# OPAMP_TESTER_1.net
KiCad netlist of a schematic drawn in Altium Designer
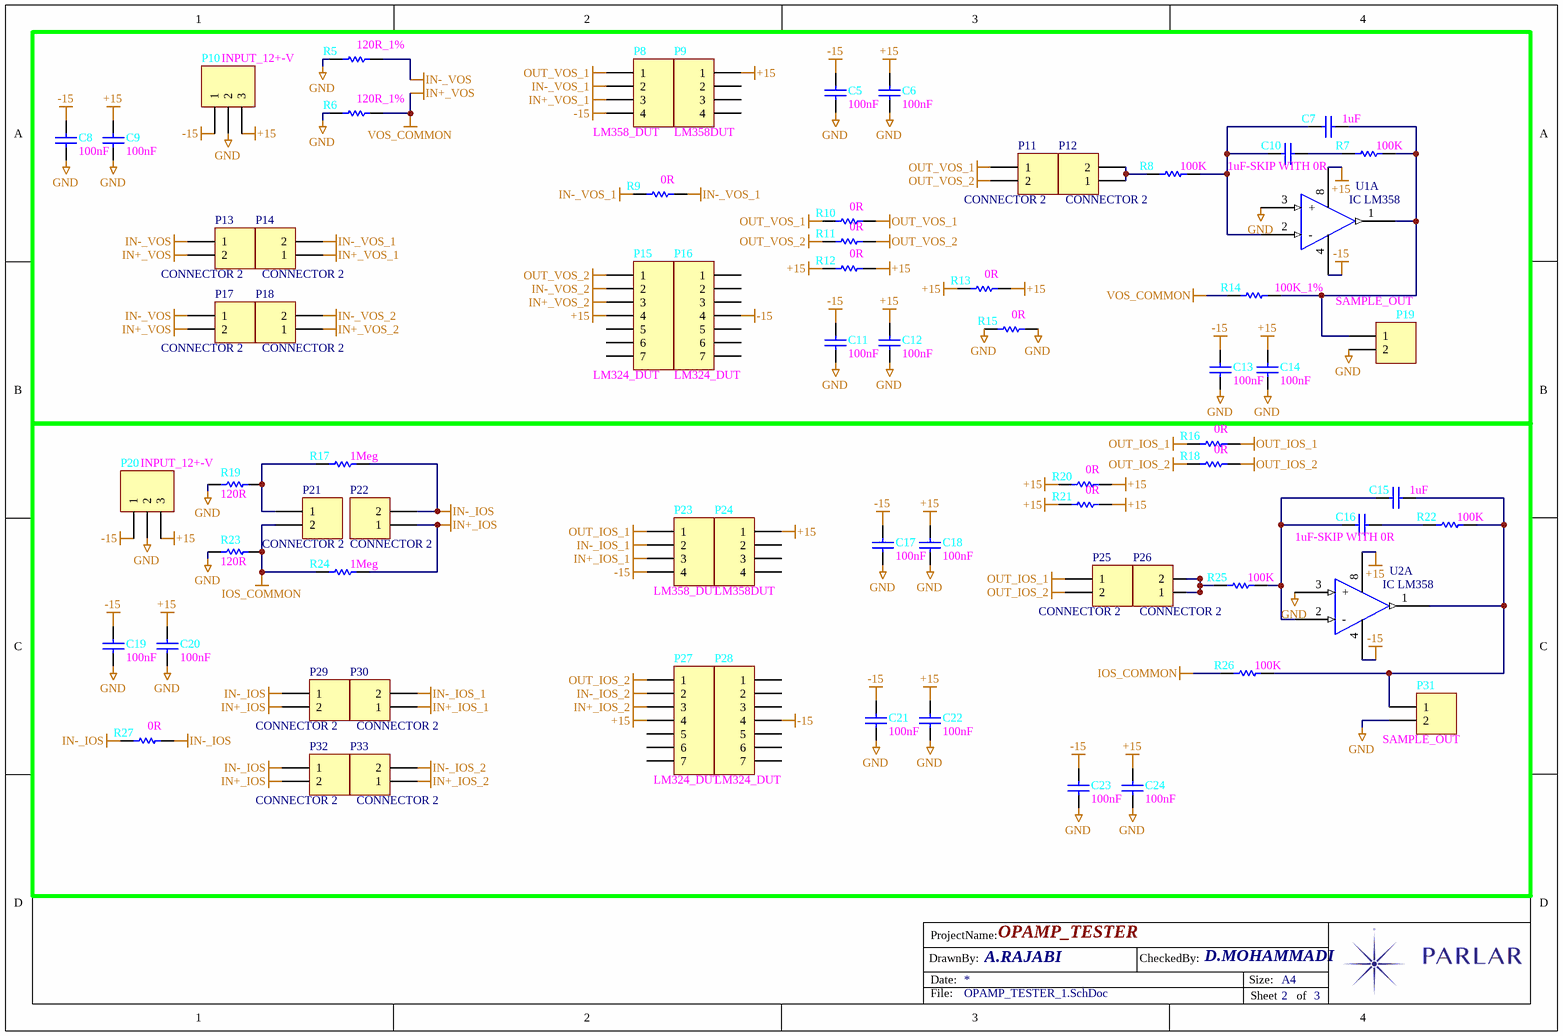
[diagram p0: OPAMP_TESTER_1.SchDoc]

(export (version "E")
  (design (tool "Eeschema 10.0.6"))
  (components
    (comp (ref "C5")
      (value "100nF")
      (footprint "SMD 0805")
      (description "Capacitor")
      (fields (field (name "PUBLISHER") "Altium Limited"))
      (libsource (lib "Parlarlib_30") (part "CAP"))
    )
    (comp (ref "C6")
      (value "100nF")
      (footprint "SMD 1206")
      (description "Capacitor")
      (fields (field (name "PUBLISHER") "Altium Limited"))
      (libsource (lib "Parlarlib_30") (part "CAP"))
    )
    (comp (ref "C7")
      (value "1uF")
      (footprint "SMD 0805")
      (description "Capacitor")
      (fields (field (name "PUBLISHER") "Altium Limited"))
      (libsource (lib "Parlarlib_30") (part "CAP"))
    )
    (comp (ref "C8")
      (value "100nF")
      (footprint "SMD 0805")
      (description "Capacitor")
      (fields (field (name "PUBLISHER") "Altium Limited"))
      (libsource (lib "Parlarlib_30") (part "CAP"))
    )
    (comp (ref "C9")
      (value "100nF")
      (footprint "SMD 0805")
      (description "Capacitor")
      (fields (field (name "PUBLISHER") "Altium Limited"))
      (libsource (lib "Parlarlib_30") (part "CAP"))
    )
    (comp (ref "C10")
      (value "1uF-SKIP WITH 0R")
      (footprint "SMD 0805")
      (description "Capacitor")
      (fields (field (name "PUBLISHER") "Altium Limited"))
      (libsource (lib "Parlarlib_30") (part "CAP"))
    )
    (comp (ref "C11")
      (value "100nF")
      (footprint "SMD 0805")
      (description "Capacitor")
      (fields (field (name "PUBLISHER") "Altium Limited"))
      (libsource (lib "Parlarlib_30") (part "CAP"))
    )
    (comp (ref "C12")
      (value "100nF")
      (footprint "SMD 1206")
      (description "Capacitor")
      (fields (field (name "PUBLISHER") "Altium Limited"))
      (libsource (lib "Parlarlib_30") (part "CAP"))
    )
    (comp (ref "C13")
      (value "100nF")
      (footprint "SMD 0805")
      (description "Capacitor")
      (fields (field (name "PUBLISHER") "Altium Limited"))
      (libsource (lib "Parlarlib_30") (part "CAP"))
    )
    (comp (ref "C14")
      (value "100nF")
      (footprint "SMD 0805")
      (description "Capacitor")
      (fields (field (name "PUBLISHER") "Altium Limited"))
      (libsource (lib "Parlarlib_30") (part "CAP"))
    )
    (comp (ref "C15")
      (value "1uF")
      (footprint "SMD 1206")
      (description "Capacitor")
      (fields (field (name "PUBLISHER") "Altium Limited"))
      (libsource (lib "Parlarlib_30") (part "CAP"))
    )
    (comp (ref "C16")
      (value "1uF-SKIP WITH 0R")
      (footprint "SMD 1206")
      (description "Capacitor")
      (fields (field (name "PUBLISHER") "Altium Limited"))
      (libsource (lib "Parlarlib_30") (part "CAP"))
    )
    (comp (ref "C17")
      (value "100nF")
      (footprint "SMD 0805")
      (description "Capacitor")
      (fields (field (name "PUBLISHER") "Altium Limited"))
      (libsource (lib "Parlarlib_30") (part "CAP"))
    )
    (comp (ref "C18")
      (value "100nF")
      (footprint "SMD 1206")
      (description "Capacitor")
      (fields (field (name "PUBLISHER") "Altium Limited"))
      (libsource (lib "Parlarlib_30") (part "CAP"))
    )
    (comp (ref "C19")
      (value "100nF")
      (footprint "SMD 0805")
      (description "Capacitor")
      (fields (field (name "PUBLISHER") "Altium Limited"))
      (libsource (lib "Parlarlib_30") (part "CAP"))
    )
    (comp (ref "C20")
      (value "100nF")
      (footprint "SMD 0805")
      (description "Capacitor")
      (fields (field (name "PUBLISHER") "Altium Limited"))
      (libsource (lib "Parlarlib_30") (part "CAP"))
    )
    (comp (ref "C21")
      (value "100nF")
      (footprint "SMD 1206")
      (description "Capacitor")
      (fields (field (name "PUBLISHER") "Altium Limited"))
      (libsource (lib "Parlarlib_30") (part "CAP"))
    )
    (comp (ref "C22")
      (value "100nF")
      (footprint "SMD 0805")
      (description "Capacitor")
      (fields (field (name "PUBLISHER") "Altium Limited"))
      (libsource (lib "Parlarlib_30") (part "CAP"))
    )
    (comp (ref "C23")
      (value "100nF")
      (footprint "SMD 0805")
      (description "Capacitor")
      (fields (field (name "PUBLISHER") "Altium Limited"))
      (libsource (lib "Parlarlib_30") (part "CAP"))
    )
    (comp (ref "C24")
      (value "100nF")
      (footprint "SMD 0805")
      (description "Capacitor")
      (fields (field (name "PUBLISHER") "Altium Limited"))
      (libsource (lib "Parlarlib_30") (part "CAP"))
    )
    (comp (ref "P8")
      (value "LM358_DUT")
      (footprint "CON HDR 2.54FM 4")
      (description "Header, 4-Pin")
      (fields (field (name "PUBLISHER") "Altium Limited"))
      (libsource (lib "") (part "CONNECTOR 4_1"))
    )
    (comp (ref "P9")
      (value "LM358DUT")
      (footprint "CON HDR 2.54FM 4")
      (description "Header, 4-Pin")
      (fields (field (name "PUBLISHER") "Altium Limited"))
      (libsource (lib "Parlarlib_30") (part "CONNECTOR 4"))
    )
    (comp (ref "P10")
      (value "INPUT_12+-V")
      (footprint "CON XH 3")
      (description "Header, 3-Pin")
      (fields (field (name "PUBLISHER") "Altium Limited"))
      (libsource (lib "Parlarlib_30") (part "CONNECTOR 3"))
    )
    (comp (ref "P11")
      (value "CONNECTOR 2")
      (footprint "CON HDR 2.54M 2")
      (description "Header, 2-Pin")
      (fields (field (name "PUBLISHER") "Altium Limited"))
      (libsource (lib "Parlarlib_33") (part "CONNECTOR 2"))
    )
    (comp (ref "P12")
      (value "CONNECTOR 2")
      (footprint "CON HDR 2.54M 2")
      (description "Header, 2-Pin")
      (fields (field (name "PUBLISHER") "Altium Limited"))
      (libsource (lib "") (part "CONNECTOR 2_1"))
    )
    (comp (ref "P13")
      (value "CONNECTOR 2")
      (footprint "CON HDR 2.54M 2")
      (description "Header, 2-Pin")
      (fields (field (name "PUBLISHER") "Altium Limited"))
      (libsource (lib "Parlarlib_33") (part "CONNECTOR 2"))
    )
    (comp (ref "P14")
      (value "CONNECTOR 2")
      (footprint "CON HDR 2.54M 2")
      (description "Header, 2-Pin")
      (fields (field (name "PUBLISHER") "Altium Limited"))
      (libsource (lib "") (part "CONNECTOR 2_1"))
    )
    (comp (ref "P15")
      (value "LM324_DUT")
      (footprint "CON HDR 2.54FM 7")
      (description "Header, 7-Pin")
      (fields (field (name "PUBLISHER") "Altium Limited"))
      (libsource (lib "Parlarlib_30") (part "CONNECTOR 7"))
    )
    (comp (ref "P16")
      (value "LM324_DUT")
      (footprint "CON HDR 2.54FM 7")
      (description "Header, 7-Pin")
      (fields (field (name "PUBLISHER") "Altium Limited"))
      (libsource (lib "") (part "CONNECTOR 7_1"))
    )
    (comp (ref "P17")
      (value "CONNECTOR 2")
      (footprint "CON HDR 2.54M 2")
      (description "Header, 2-Pin")
      (fields (field (name "PUBLISHER") "Altium Limited"))
      (libsource (lib "Parlarlib_33") (part "CONNECTOR 2"))
    )
    (comp (ref "P18")
      (value "CONNECTOR 2")
      (footprint "CON HDR 2.54M 2")
      (description "Header, 2-Pin")
      (fields (field (name "PUBLISHER") "Altium Limited"))
      (libsource (lib "") (part "CONNECTOR 2_1"))
    )
    (comp (ref "P19")
      (value "SAMPLE_OUT")
      (footprint "CON XH 2")
      (description "Header, 2-Pin")
      (fields (field (name "PUBLISHER") "Altium Limited"))
      (libsource (lib "Parlarlib_30") (part "CONNECTOR 2"))
    )
    (comp (ref "P20")
      (value "INPUT_12+-V")
      (footprint "CON XH 3")
      (description "Header, 3-Pin")
      (fields (field (name "PUBLISHER") "Altium Limited"))
      (libsource (lib "Parlarlib_30") (part "CONNECTOR 3"))
    )
    (comp (ref "P21")
      (value "CONNECTOR 2")
      (footprint "CON HDR 2.54M 2")
      (description "Header, 2-Pin")
      (fields (field (name "PUBLISHER") "Altium Limited"))
      (libsource (lib "Parlarlib_33") (part "CONNECTOR 2"))
    )
    (comp (ref "P22")
      (value "CONNECTOR 2")
      (footprint "CON HDR 2.54M 2")
      (description "Header, 2-Pin")
      (fields (field (name "PUBLISHER") "Altium Limited"))
      (libsource (lib "") (part "CONNECTOR 2_1"))
    )
    (comp (ref "P23")
      (value "LM358_DUT")
      (footprint "CON HDR 2.54FM 4")
      (description "Header, 4-Pin")
      (fields (field (name "PUBLISHER") "Altium Limited"))
      (libsource (lib "") (part "CONNECTOR 4_1"))
    )
    (comp (ref "P24")
      (value "LM358DUT")
      (footprint "CON HDR 2.54FM 4")
      (description "Header, 4-Pin")
      (fields (field (name "PUBLISHER") "Altium Limited"))
      (libsource (lib "Parlarlib_30") (part "CONNECTOR 4"))
    )
    (comp (ref "P25")
      (value "CONNECTOR 2")
      (footprint "CON HDR 2.54M 2")
      (description "Header, 2-Pin")
      (fields (field (name "PUBLISHER") "Altium Limited"))
      (libsource (lib "Parlarlib_33") (part "CONNECTOR 2"))
    )
    (comp (ref "P26")
      (value "CONNECTOR 2")
      (footprint "CON HDR 2.54M 2")
      (description "Header, 2-Pin")
      (fields (field (name "PUBLISHER") "Altium Limited"))
      (libsource (lib "") (part "CONNECTOR 2_1"))
    )
    (comp (ref "P27")
      (value "LM324_DUT")
      (footprint "CON HDR 2.54FM 7")
      (description "Header, 7-Pin")
      (fields (field (name "PUBLISHER") "Altium Limited"))
      (libsource (lib "Parlarlib_30") (part "CONNECTOR 7"))
    )
    (comp (ref "P28")
      (value "LM324_DUT")
      (footprint "CON HDR 2.54FM 7")
      (description "Header, 7-Pin")
      (fields (field (name "PUBLISHER") "Altium Limited"))
      (libsource (lib "") (part "CONNECTOR 7_1"))
    )
    (comp (ref "P29")
      (value "CONNECTOR 2")
      (footprint "CON HDR 2.54M 2")
      (description "Header, 2-Pin")
      (fields (field (name "PUBLISHER") "Altium Limited"))
      (libsource (lib "Parlarlib_33") (part "CONNECTOR 2"))
    )
    (comp (ref "P30")
      (value "CONNECTOR 2")
      (footprint "CON HDR 2.54M 2")
      (description "Header, 2-Pin")
      (fields (field (name "PUBLISHER") "Altium Limited"))
      (libsource (lib "") (part "CONNECTOR 2_1"))
    )
    (comp (ref "P31")
      (value "SAMPLE_OUT")
      (footprint "CON XH 2")
      (description "Header, 2-Pin")
      (fields (field (name "PUBLISHER") "Altium Limited"))
      (libsource (lib "Parlarlib_30") (part "CONNECTOR 2"))
    )
    (comp (ref "P32")
      (value "CONNECTOR 2")
      (footprint "CON HDR 2.54M 2")
      (description "Header, 2-Pin")
      (fields (field (name "PUBLISHER") "Altium Limited"))
      (libsource (lib "Parlarlib_33") (part "CONNECTOR 2"))
    )
    (comp (ref "P33")
      (value "CONNECTOR 2")
      (footprint "CON HDR 2.54M 2")
      (description "Header, 2-Pin")
      (fields (field (name "PUBLISHER") "Altium Limited"))
      (libsource (lib "") (part "CONNECTOR 2_1"))
    )
    (comp (ref "R5")
      (value "120R_1%")
      (footprint "SMD 1206")
      (description "Resistor")
      (libsource (lib "Parlarlib_30") (part "RES"))
    )
    (comp (ref "R6")
      (value "120R_1%")
      (footprint "SMD 0805")
      (description "Resistor")
      (libsource (lib "Parlarlib_30") (part "RES"))
    )
    (comp (ref "R7")
      (value "100K")
      (footprint "SMD 0805")
      (description "Resistor")
      (libsource (lib "Parlarlib_30") (part "RES"))
    )
    (comp (ref "R8")
      (value "100K")
      (footprint "SMD 1206")
      (description "Resistor")
      (libsource (lib "Parlarlib_30") (part "RES"))
    )
    (comp (ref "R9")
      (value "0R")
      (footprint "SMD 1206")
      (description "Resistor")
      (libsource (lib "Parlarlib_30") (part "RES"))
    )
    (comp (ref "R10")
      (value "0R")
      (footprint "SMD 1206")
      (description "Resistor")
      (libsource (lib "Parlarlib_30") (part "RES"))
    )
    (comp (ref "R11")
      (value "0R")
      (footprint "SMD 1206")
      (description "Resistor")
      (libsource (lib "Parlarlib_30") (part "RES"))
    )
    (comp (ref "R12")
      (value "0R")
      (footprint "SMD 1206")
      (description "Resistor")
      (libsource (lib "Parlarlib_30") (part "RES"))
    )
    (comp (ref "R13")
      (value "0R")
      (footprint "SMD 1206")
      (description "Resistor")
      (libsource (lib "Parlarlib_30") (part "RES"))
    )
    (comp (ref "R14")
      (value "100K_1%")
      (footprint "SMD 1206")
      (description "Resistor")
      (libsource (lib "Parlarlib_30") (part "RES"))
    )
    (comp (ref "R15")
      (value "0R")
      (footprint "SMD 1206")
      (description "Resistor")
      (libsource (lib "Parlarlib_30") (part "RES"))
    )
    (comp (ref "R16")
      (value "0R")
      (footprint "SMD 1206")
      (description "Resistor")
      (libsource (lib "Parlarlib_30") (part "RES"))
    )
    (comp (ref "R17")
      (value "1Meg")
      (footprint "SMD 0805")
      (description "Resistor")
      (libsource (lib "Parlarlib_30") (part "RES"))
    )
    (comp (ref "R18")
      (value "0R")
      (footprint "SMD 1206")
      (description "Resistor")
      (libsource (lib "Parlarlib_30") (part "RES"))
    )
    (comp (ref "R19")
      (value "120R")
      (footprint "SMD 0805")
      (description "Resistor")
      (libsource (lib "Parlarlib_30") (part "RES"))
    )
    (comp (ref "R20")
      (value "0R")
      (footprint "SMD 1206")
      (description "Resistor")
      (libsource (lib "Parlarlib_30") (part "RES"))
    )
    (comp (ref "R21")
      (value "0R")
      (footprint "SMD 1206")
      (description "Resistor")
      (libsource (lib "Parlarlib_30") (part "RES"))
    )
    (comp (ref "R22")
      (value "100K")
      (footprint "SMD 0805")
      (description "Resistor")
      (libsource (lib "Parlarlib_30") (part "RES"))
    )
    (comp (ref "R23")
      (value "120R")
      (footprint "SMD 0805")
      (description "Resistor")
      (libsource (lib "Parlarlib_30") (part "RES"))
    )
    (comp (ref "R24")
      (value "1Meg")
      (footprint "SMD 0805")
      (description "Resistor")
      (libsource (lib "Parlarlib_30") (part "RES"))
    )
    (comp (ref "R25")
      (value "100K")
      (footprint "SMD 1206")
      (description "Resistor")
      (libsource (lib "Parlarlib_30") (part "RES"))
    )
    (comp (ref "R26")
      (value "100K")
      (footprint "SMD 0805")
      (description "Resistor")
      (libsource (lib "Parlarlib_30") (part "RES"))
    )
    (comp (ref "R27")
      (value "0R")
      (footprint "SMD 1206")
      (description "Resistor")
      (libsource (lib "Parlarlib_30") (part "RES"))
    )
    (comp (ref "U1")
      (value "IC LM358")
      (footprint "SMD IC SOP8")
      (libsource (lib "Parlarlib_33") (part "IC LM358"))
    )
    (comp (ref "U2")
      (value "IC LM358")
      (footprint "SMD IC SOP8")
      (libsource (lib "Parlarlib_33") (part "IC LM358"))
    )
  )
  (nets
    (net (code "1") (name "+15") (class "Default")
      (node (ref "C12") (pin "2") (pinfunction "2_2") (pintype "passive"))
      (node (ref "C14") (pin "2") (pinfunction "2_2") (pintype "passive"))
      (node (ref "C18") (pin "2") (pinfunction "2_2") (pintype "passive"))
      (node (ref "C20") (pin "2") (pinfunction "2_2") (pintype "passive"))
      (node (ref "C22") (pin "2") (pinfunction "2_2") (pintype "passive"))
      (node (ref "C24") (pin "2") (pinfunction "2_2") (pintype "passive"))
      (node (ref "C6") (pin "2") (pinfunction "2_2") (pintype "passive"))
      (node (ref "C9") (pin "2") (pinfunction "2_2") (pintype "passive"))
      (node (ref "P10") (pin "3") (pinfunction "3_3") (pintype "passive"))
      (node (ref "P15") (pin "4") (pinfunction "4_4") (pintype "passive"))
      (node (ref "P20") (pin "3") (pinfunction "3_3") (pintype "passive"))
      (node (ref "P24") (pin "1") (pinfunction "1_1") (pintype "passive"))
      (node (ref "P27") (pin "4") (pinfunction "4_4") (pintype "passive"))
      (node (ref "P9") (pin "1") (pinfunction "1_1") (pintype "passive"))
      (node (ref "R12") (pin "1") (pinfunction "1_1") (pintype "passive"))
      (node (ref "R12") (pin "2") (pinfunction "2_2") (pintype "passive"))
      (node (ref "R13") (pin "1") (pinfunction "1_1") (pintype "passive"))
      (node (ref "R13") (pin "2") (pinfunction "2_2") (pintype "passive"))
      (node (ref "R20") (pin "1") (pinfunction "1_1") (pintype "passive"))
      (node (ref "R20") (pin "2") (pinfunction "2_2") (pintype "passive"))
      (node (ref "R21") (pin "1") (pinfunction "1_1") (pintype "passive"))
      (node (ref "R21") (pin "2") (pinfunction "2_2") (pintype "passive"))
      (node (ref "U1") (pin "8") (pinfunction "VCC_8") (pintype "passive"))
      (node (ref "U2") (pin "8") (pinfunction "VCC_8") (pintype "passive"))
    )
    (net (code "2") (name "-15") (class "Default")
      (node (ref "C11") (pin "2") (pinfunction "2_2") (pintype "passive"))
      (node (ref "C13") (pin "2") (pinfunction "2_2") (pintype "passive"))
      (node (ref "C17") (pin "2") (pinfunction "2_2") (pintype "passive"))
      (node (ref "C19") (pin "2") (pinfunction "2_2") (pintype "passive"))
      (node (ref "C21") (pin "2") (pinfunction "2_2") (pintype "passive"))
      (node (ref "C23") (pin "2") (pinfunction "2_2") (pintype "passive"))
      (node (ref "C5") (pin "2") (pinfunction "2_2") (pintype "passive"))
      (node (ref "C8") (pin "2") (pinfunction "2_2") (pintype "passive"))
      (node (ref "P10") (pin "1") (pinfunction "1_1") (pintype "passive"))
      (node (ref "P16") (pin "4") (pinfunction "4_4") (pintype "passive"))
      (node (ref "P20") (pin "1") (pinfunction "1_1") (pintype "passive"))
      (node (ref "P23") (pin "4") (pinfunction "4_4") (pintype "passive"))
      (node (ref "P28") (pin "4") (pinfunction "4_4") (pintype "passive"))
      (node (ref "P8") (pin "4") (pinfunction "4_4") (pintype "passive"))
      (node (ref "U1") (pin "4") (pinfunction "GND_4") (pintype "passive"))
      (node (ref "U2") (pin "4") (pinfunction "GND_4") (pintype "passive"))
    )
    (net (code "3") (name "GND") (class "Default")
      (node (ref "C11") (pin "1") (pinfunction "1_1") (pintype "passive"))
      (node (ref "C12") (pin "1") (pinfunction "1_1") (pintype "passive"))
      (node (ref "C13") (pin "1") (pinfunction "1_1") (pintype "passive"))
      (node (ref "C14") (pin "1") (pinfunction "1_1") (pintype "passive"))
      (node (ref "C17") (pin "1") (pinfunction "1_1") (pintype "passive"))
      (node (ref "C18") (pin "1") (pinfunction "1_1") (pintype "passive"))
      (node (ref "C19") (pin "1") (pinfunction "1_1") (pintype "passive"))
      (node (ref "C20") (pin "1") (pinfunction "1_1") (pintype "passive"))
      (node (ref "C21") (pin "1") (pinfunction "1_1") (pintype "passive"))
      (node (ref "C22") (pin "1") (pinfunction "1_1") (pintype "passive"))
      (node (ref "C23") (pin "1") (pinfunction "1_1") (pintype "passive"))
      (node (ref "C24") (pin "1") (pinfunction "1_1") (pintype "passive"))
      (node (ref "C5") (pin "1") (pinfunction "1_1") (pintype "passive"))
      (node (ref "C6") (pin "1") (pinfunction "1_1") (pintype "passive"))
      (node (ref "C8") (pin "1") (pinfunction "1_1") (pintype "passive"))
      (node (ref "C9") (pin "1") (pinfunction "1_1") (pintype "passive"))
      (node (ref "P10") (pin "2") (pinfunction "2_2") (pintype "passive"))
      (node (ref "P19") (pin "2") (pinfunction "2_2") (pintype "passive"))
      (node (ref "P20") (pin "2") (pinfunction "2_2") (pintype "passive"))
      (node (ref "P31") (pin "2") (pinfunction "2_2") (pintype "passive"))
      (node (ref "R15") (pin "1") (pinfunction "1_1") (pintype "passive"))
      (node (ref "R15") (pin "2") (pinfunction "2_2") (pintype "passive"))
      (node (ref "R19") (pin "1") (pinfunction "1_1") (pintype "passive"))
      (node (ref "R23") (pin "1") (pinfunction "1_1") (pintype "passive"))
      (node (ref "R5") (pin "1") (pinfunction "1_1") (pintype "passive"))
      (node (ref "R6") (pin "1") (pinfunction "1_1") (pintype "passive"))
      (node (ref "U1") (pin "3") (pinfunction "+_3") (pintype "input"))
      (node (ref "U2") (pin "3") (pinfunction "+_3") (pintype "input"))
    )
    (net (code "4") (name "IN+_IOS") (class "Default")
      (node (ref "P22") (pin "1") (pinfunction "1_1") (pintype "passive"))
      (node (ref "P29") (pin "2") (pinfunction "2_2") (pintype "passive"))
      (node (ref "P32") (pin "2") (pinfunction "2_2") (pintype "passive"))
      (node (ref "R24") (pin "2") (pinfunction "2_2") (pintype "passive"))
    )
    (net (code "5") (name "IN+_IOS_1") (class "Default")
      (node (ref "P23") (pin "3") (pinfunction "3_3") (pintype "passive"))
      (node (ref "P30") (pin "1") (pinfunction "1_1") (pintype "passive"))
    )
    (net (code "6") (name "IN+_IOS_2") (class "Default")
      (node (ref "P27") (pin "3") (pinfunction "3_3") (pintype "passive"))
      (node (ref "P33") (pin "1") (pinfunction "1_1") (pintype "passive"))
    )
    (net (code "7") (name "IN+_VOS") (class "Default")
      (node (ref "P13") (pin "2") (pinfunction "2_2") (pintype "passive"))
      (node (ref "P17") (pin "2") (pinfunction "2_2") (pintype "passive"))
      (node (ref "R14") (pin "1") (pinfunction "1_1") (pintype "passive"))
      (node (ref "R6") (pin "2") (pinfunction "2_2") (pintype "passive"))
    )
    (net (code "8") (name "IN+_VOS_1") (class "Default")
      (node (ref "P14") (pin "1") (pinfunction "1_1") (pintype "passive"))
      (node (ref "P8") (pin "3") (pinfunction "3_3") (pintype "passive"))
    )
    (net (code "9") (name "IN+_VOS_2") (class "Default")
      (node (ref "P15") (pin "3") (pinfunction "3_3") (pintype "passive"))
      (node (ref "P18") (pin "1") (pinfunction "1_1") (pintype "passive"))
    )
    (net (code "10") (name "IN-_IOS") (class "Default")
      (node (ref "P22") (pin "2") (pinfunction "2_2") (pintype "passive"))
      (node (ref "P29") (pin "1") (pinfunction "1_1") (pintype "passive"))
      (node (ref "P32") (pin "1") (pinfunction "1_1") (pintype "passive"))
      (node (ref "R17") (pin "2") (pinfunction "2_2") (pintype "passive"))
      (node (ref "R27") (pin "1") (pinfunction "1_1") (pintype "passive"))
      (node (ref "R27") (pin "2") (pinfunction "2_2") (pintype "passive"))
    )
    (net (code "11") (name "IN-_IOS_1") (class "Default")
      (node (ref "P23") (pin "2") (pinfunction "2_2") (pintype "passive"))
      (node (ref "P30") (pin "2") (pinfunction "2_2") (pintype "passive"))
    )
    (net (code "12") (name "IN-_IOS_2") (class "Default")
      (node (ref "P27") (pin "2") (pinfunction "2_2") (pintype "passive"))
      (node (ref "P33") (pin "2") (pinfunction "2_2") (pintype "passive"))
    )
    (net (code "13") (name "IN-_VOS") (class "Default")
      (node (ref "P13") (pin "1") (pinfunction "1_1") (pintype "passive"))
      (node (ref "P17") (pin "1") (pinfunction "1_1") (pintype "passive"))
      (node (ref "R5") (pin "2") (pinfunction "2_2") (pintype "passive"))
    )
    (net (code "14") (name "IN-_VOS_1") (class "Default")
      (node (ref "P14") (pin "2") (pinfunction "2_2") (pintype "passive"))
      (node (ref "P8") (pin "2") (pinfunction "2_2") (pintype "passive"))
      (node (ref "R9") (pin "1") (pinfunction "1_1") (pintype "passive"))
      (node (ref "R9") (pin "2") (pinfunction "2_2") (pintype "passive"))
    )
    (net (code "15") (name "IN-_VOS_2") (class "Default")
      (node (ref "P15") (pin "2") (pinfunction "2_2") (pintype "passive"))
      (node (ref "P18") (pin "2") (pinfunction "2_2") (pintype "passive"))
    )
    (net (code "16") (name "IOS_COMMON") (class "Default")
      (node (ref "P21") (pin "2") (pinfunction "2_2") (pintype "passive"))
      (node (ref "R23") (pin "2") (pinfunction "2_2") (pintype "passive"))
      (node (ref "R24") (pin "1") (pinfunction "1_1") (pintype "passive"))
      (node (ref "R26") (pin "1") (pinfunction "1_1") (pintype "passive"))
    )
    (net (code "17") (name "Net-(C10-Pad1)") (class "Default")
      (node (ref "C10") (pin "1") (pinfunction "1_1") (pintype "passive"))
      (node (ref "R7") (pin "1") (pinfunction "1_1") (pintype "passive"))
    )
    (net (code "18") (name "Net-(C16-Pad1)") (class "Default")
      (node (ref "C16") (pin "1") (pinfunction "1_1") (pintype "passive"))
      (node (ref "R22") (pin "1") (pinfunction "1_1") (pintype "passive"))
    )
    (net (code "19") (name "Net-(P12-Pad1)") (class "Default")
      (node (ref "P12") (pin "1") (pinfunction "1_1") (pintype "passive"))
      (node (ref "P12") (pin "2") (pinfunction "2_2") (pintype "passive"))
      (node (ref "R8") (pin "1") (pinfunction "1_1") (pintype "passive"))
    )
    (net (code "20") (name "Net-(P21-Pad1)") (class "Default")
      (node (ref "P21") (pin "1") (pinfunction "1_1") (pintype "passive"))
      (node (ref "R17") (pin "1") (pinfunction "1_1") (pintype "passive"))
      (node (ref "R19") (pin "2") (pinfunction "2_2") (pintype "passive"))
    )
    (net (code "21") (name "Net-(P26-Pad1)") (class "Default")
      (node (ref "P26") (pin "1") (pinfunction "1_1") (pintype "passive"))
      (node (ref "P26") (pin "2") (pinfunction "2_2") (pintype "passive"))
      (node (ref "R25") (pin "1") (pinfunction "1_1") (pintype "passive"))
    )
    (net (code "22") (name "Net-(U1A--)") (class "Default")
      (node (ref "C10") (pin "2") (pinfunction "2_2") (pintype "passive"))
      (node (ref "C7") (pin "2") (pinfunction "2_2") (pintype "passive"))
      (node (ref "R8") (pin "2") (pinfunction "2_2") (pintype "passive"))
      (node (ref "U1") (pin "2") (pinfunction "-_2") (pintype "input"))
    )
    (net (code "23") (name "Net-(U1A-OUT1)") (class "Default")
      (node (ref "C7") (pin "1") (pinfunction "1_1") (pintype "passive"))
      (node (ref "P19") (pin "1") (pinfunction "1_1") (pintype "passive"))
      (node (ref "R14") (pin "2") (pinfunction "2_2") (pintype "passive"))
      (node (ref "R7") (pin "2") (pinfunction "2_2") (pintype "passive"))
      (node (ref "U1") (pin "1") (pinfunction "OUT1_1") (pintype "output"))
    )
    (net (code "24") (name "Net-(U2A--)") (class "Default")
      (node (ref "C15") (pin "2") (pinfunction "2_2") (pintype "passive"))
      (node (ref "C16") (pin "2") (pinfunction "2_2") (pintype "passive"))
      (node (ref "R25") (pin "2") (pinfunction "2_2") (pintype "passive"))
      (node (ref "U2") (pin "2") (pinfunction "-_2") (pintype "input"))
    )
    (net (code "25") (name "Net-(U2A-OUT1)") (class "Default")
      (node (ref "C15") (pin "1") (pinfunction "1_1") (pintype "passive"))
      (node (ref "P31") (pin "1") (pinfunction "1_1") (pintype "passive"))
      (node (ref "R22") (pin "2") (pinfunction "2_2") (pintype "passive"))
      (node (ref "R26") (pin "2") (pinfunction "2_2") (pintype "passive"))
      (node (ref "U2") (pin "1") (pinfunction "OUT1_1") (pintype "output"))
    )
    (net (code "26") (name "OUT_IOS_1") (class "Default")
      (node (ref "P23") (pin "1") (pinfunction "1_1") (pintype "passive"))
      (node (ref "P25") (pin "1") (pinfunction "1_1") (pintype "passive"))
      (node (ref "R16") (pin "1") (pinfunction "1_1") (pintype "passive"))
      (node (ref "R16") (pin "2") (pinfunction "2_2") (pintype "passive"))
    )
    (net (code "27") (name "OUT_IOS_2") (class "Default")
      (node (ref "P25") (pin "2") (pinfunction "2_2") (pintype "passive"))
      (node (ref "P27") (pin "1") (pinfunction "1_1") (pintype "passive"))
      (node (ref "R18") (pin "1") (pinfunction "1_1") (pintype "passive"))
      (node (ref "R18") (pin "2") (pinfunction "2_2") (pintype "passive"))
    )
    (net (code "28") (name "OUT_VOS_1") (class "Default")
      (node (ref "P11") (pin "1") (pinfunction "1_1") (pintype "passive"))
      (node (ref "P8") (pin "1") (pinfunction "1_1") (pintype "passive"))
      (node (ref "R10") (pin "1") (pinfunction "1_1") (pintype "passive"))
      (node (ref "R10") (pin "2") (pinfunction "2_2") (pintype "passive"))
    )
    (net (code "29") (name "OUT_VOS_2") (class "Default")
      (node (ref "P11") (pin "2") (pinfunction "2_2") (pintype "passive"))
      (node (ref "P15") (pin "1") (pinfunction "1_1") (pintype "passive"))
      (node (ref "R11") (pin "1") (pinfunction "1_1") (pintype "passive"))
      (node (ref "R11") (pin "2") (pinfunction "2_2") (pintype "passive"))
    )
    (net (code "30") (name "unconnected-(P9-Pad2)") (class "Default")
      (node (ref "P9") (pin "2") (pinfunction "2_2") (pintype "passive"))
    )
    (net (code "31") (name "unconnected-(P9-Pad3)") (class "Default")
      (node (ref "P9") (pin "3") (pinfunction "3_3") (pintype "passive"))
    )
    (net (code "32") (name "unconnected-(P9-Pad4)") (class "Default")
      (node (ref "P9") (pin "4") (pinfunction "4_4") (pintype "passive"))
    )
    (net (code "33") (name "unconnected-(P15-Pad5)") (class "Default")
      (node (ref "P15") (pin "5") (pinfunction "5_5") (pintype "passive"))
    )
    (net (code "34") (name "unconnected-(P15-Pad6)") (class "Default")
      (node (ref "P15") (pin "6") (pinfunction "6_6") (pintype "passive"))
    )
    (net (code "35") (name "unconnected-(P15-Pad7)") (class "Default")
      (node (ref "P15") (pin "7") (pinfunction "7_7") (pintype "passive"))
    )
    (net (code "36") (name "unconnected-(P16-Pad1)") (class "Default")
      (node (ref "P16") (pin "1") (pinfunction "1_1") (pintype "passive"))
    )
    (net (code "37") (name "unconnected-(P16-Pad2)") (class "Default")
      (node (ref "P16") (pin "2") (pinfunction "2_2") (pintype "passive"))
    )
    (net (code "38") (name "unconnected-(P16-Pad3)") (class "Default")
      (node (ref "P16") (pin "3") (pinfunction "3_3") (pintype "passive"))
    )
    (net (code "39") (name "unconnected-(P16-Pad5)") (class "Default")
      (node (ref "P16") (pin "5") (pinfunction "5_5") (pintype "passive"))
    )
    (net (code "40") (name "unconnected-(P16-Pad6)") (class "Default")
      (node (ref "P16") (pin "6") (pinfunction "6_6") (pintype "passive"))
    )
    (net (code "41") (name "unconnected-(P16-Pad7)") (class "Default")
      (node (ref "P16") (pin "7") (pinfunction "7_7") (pintype "passive"))
    )
    (net (code "42") (name "unconnected-(P24-Pad2)") (class "Default")
      (node (ref "P24") (pin "2") (pinfunction "2_2") (pintype "passive"))
    )
    (net (code "43") (name "unconnected-(P24-Pad3)") (class "Default")
      (node (ref "P24") (pin "3") (pinfunction "3_3") (pintype "passive"))
    )
    (net (code "44") (name "unconnected-(P24-Pad4)") (class "Default")
      (node (ref "P24") (pin "4") (pinfunction "4_4") (pintype "passive"))
    )
    (net (code "45") (name "unconnected-(P27-Pad5)") (class "Default")
      (node (ref "P27") (pin "5") (pinfunction "5_5") (pintype "passive"))
    )
    (net (code "46") (name "unconnected-(P27-Pad6)") (class "Default")
      (node (ref "P27") (pin "6") (pinfunction "6_6") (pintype "passive"))
    )
    (net (code "47") (name "unconnected-(P27-Pad7)") (class "Default")
      (node (ref "P27") (pin "7") (pinfunction "7_7") (pintype "passive"))
    )
    (net (code "48") (name "unconnected-(P28-Pad1)") (class "Default")
      (node (ref "P28") (pin "1") (pinfunction "1_1") (pintype "passive"))
    )
    (net (code "49") (name "unconnected-(P28-Pad2)") (class "Default")
      (node (ref "P28") (pin "2") (pinfunction "2_2") (pintype "passive"))
    )
    (net (code "50") (name "unconnected-(P28-Pad3)") (class "Default")
      (node (ref "P28") (pin "3") (pinfunction "3_3") (pintype "passive"))
    )
    (net (code "51") (name "unconnected-(P28-Pad5)") (class "Default")
      (node (ref "P28") (pin "5") (pinfunction "5_5") (pintype "passive"))
    )
    (net (code "52") (name "unconnected-(P28-Pad6)") (class "Default")
      (node (ref "P28") (pin "6") (pinfunction "6_6") (pintype "passive"))
    )
    (net (code "53") (name "unconnected-(P28-Pad7)") (class "Default")
      (node (ref "P28") (pin "7") (pinfunction "7_7") (pintype "passive"))
    )
  )
)
